# power.net
KiCad netlist of a schematic drawn in EAGLE
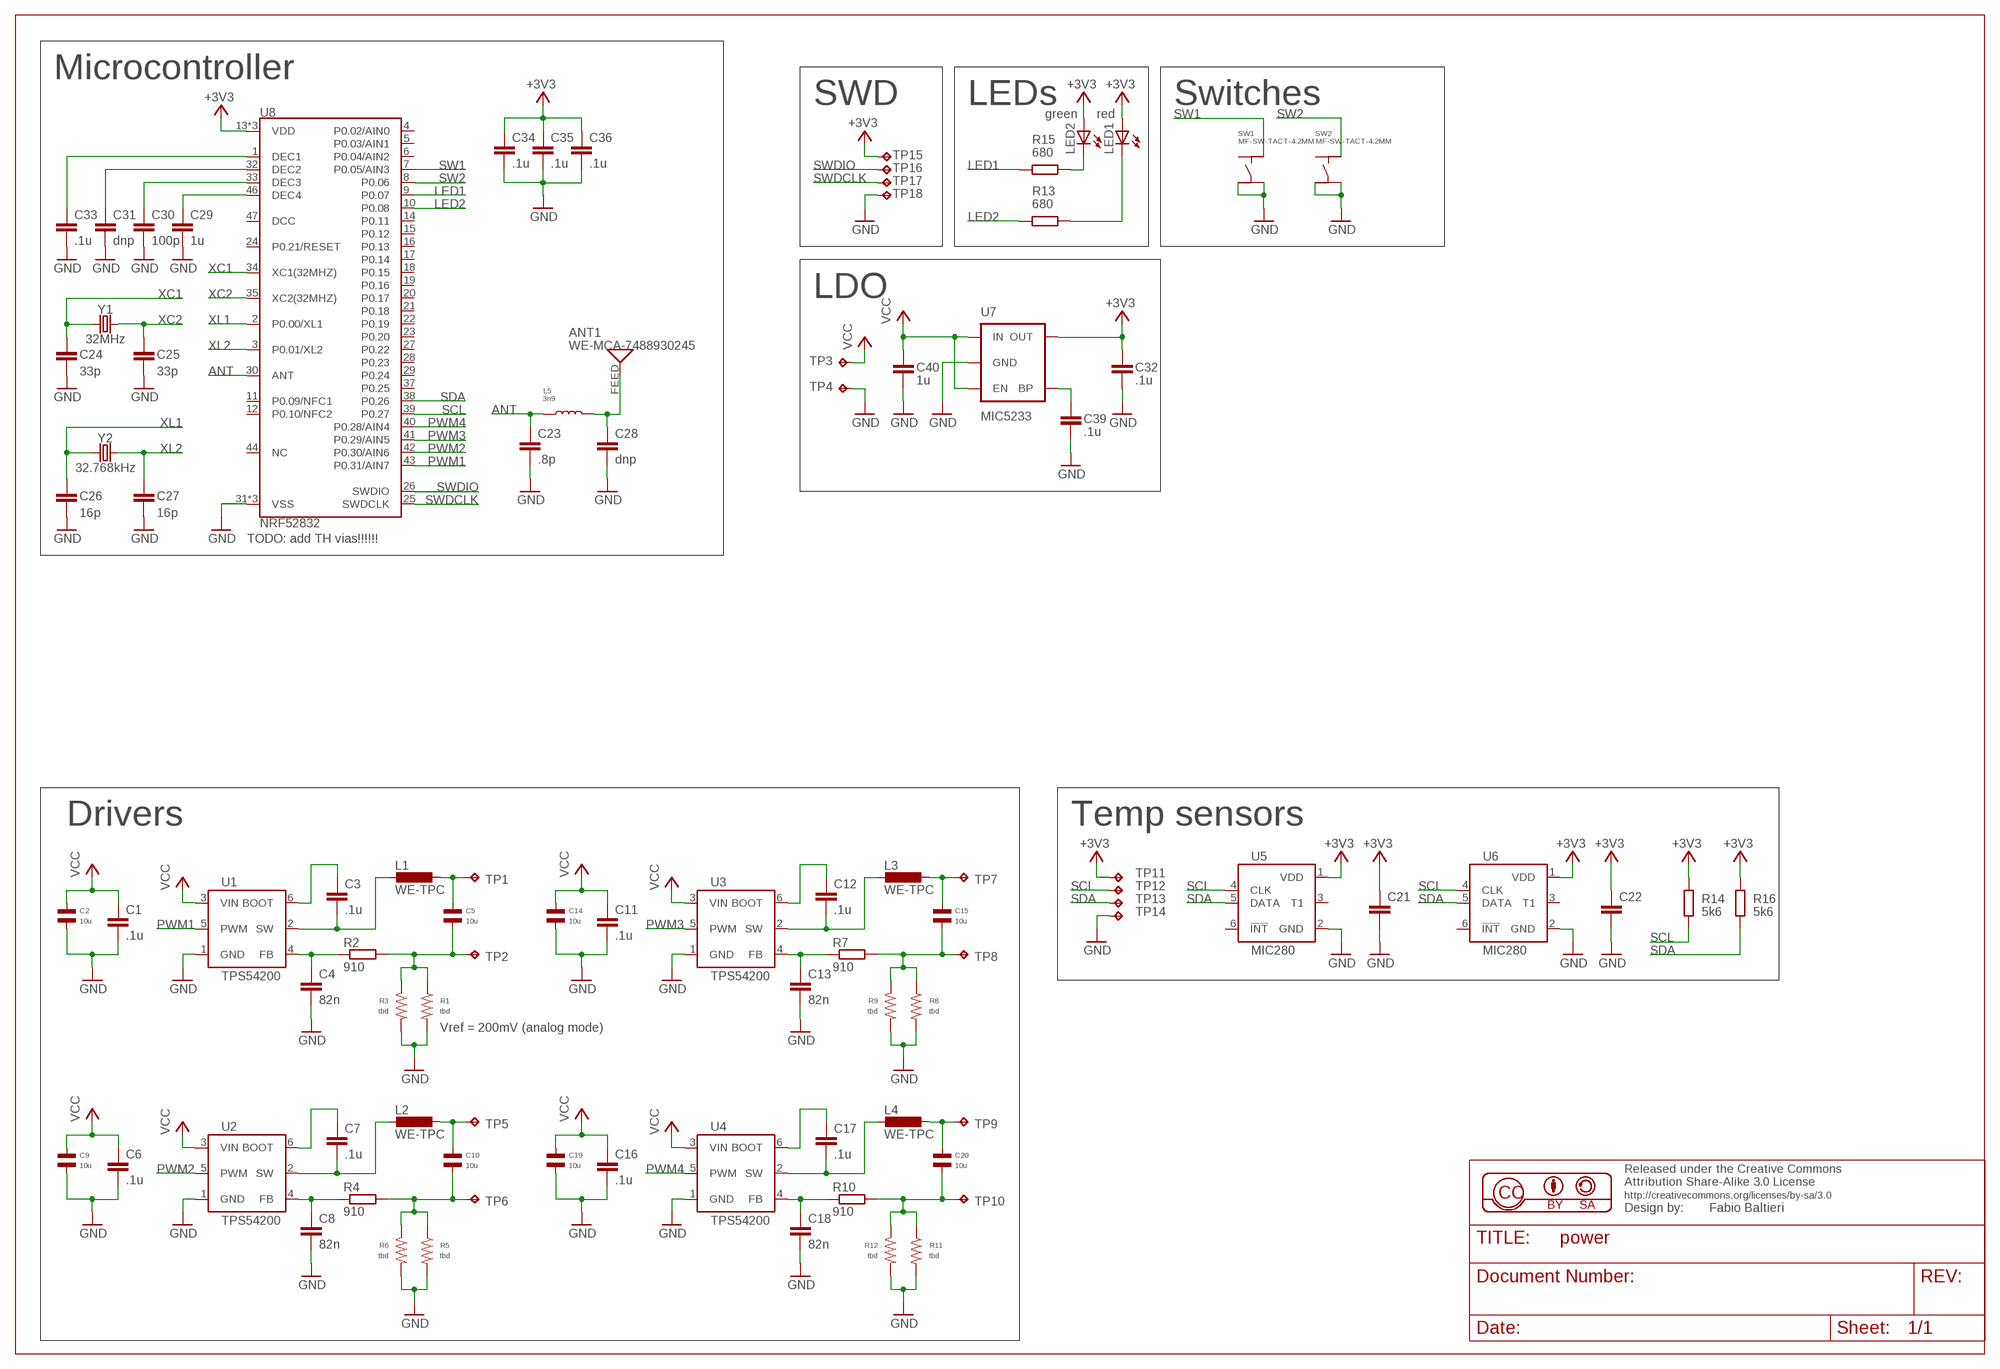
[diagram p0: schematic, sheet 1]

(export (version "E")
  (design (tool "Eeschema 10.0.6"))
  (components
    (comp (ref "ANT1")
      (value "WE-MCA-7488930245")
      (footprint "eagle-import:WE-MCA")
      (libsource (lib "eagle-import") (part "WE-MCA-7488930245"))
    )
    (comp (ref "C1")
      (value ".1u")
      (footprint "eagle-import:0603")
      (libsource (lib "eagle-import") (part "C0603"))
    )
    (comp (ref "C2")
      (value "10u")
      (footprint "eagle-import:C1206")
      (libsource (lib "eagle-import") (part "CAPACITOR_NP_1206"))
    )
    (comp (ref "C3")
      (value ".1u")
      (footprint "eagle-import:0603")
      (libsource (lib "eagle-import") (part "C0603"))
    )
    (comp (ref "C4")
      (value "82n")
      (footprint "eagle-import:0603")
      (libsource (lib "eagle-import") (part "C0603"))
    )
    (comp (ref "C5")
      (value "10u")
      (footprint "eagle-import:C1206")
      (libsource (lib "eagle-import") (part "CAPACITOR_NP_1206"))
    )
    (comp (ref "C6")
      (value ".1u")
      (footprint "eagle-import:0603")
      (libsource (lib "eagle-import") (part "C0603"))
    )
    (comp (ref "C7")
      (value ".1u")
      (footprint "eagle-import:0603")
      (libsource (lib "eagle-import") (part "C0603"))
    )
    (comp (ref "C8")
      (value "82n")
      (footprint "eagle-import:0603")
      (libsource (lib "eagle-import") (part "C0603"))
    )
    (comp (ref "C9")
      (value "10u")
      (footprint "eagle-import:C1206")
      (libsource (lib "eagle-import") (part "CAPACITOR_NP_1206"))
    )
    (comp (ref "C10")
      (value "10u")
      (footprint "eagle-import:C1206")
      (libsource (lib "eagle-import") (part "CAPACITOR_NP_1206"))
    )
    (comp (ref "C11")
      (value ".1u")
      (footprint "eagle-import:0603")
      (libsource (lib "eagle-import") (part "C0603"))
    )
    (comp (ref "C12")
      (value ".1u")
      (footprint "eagle-import:0603")
      (libsource (lib "eagle-import") (part "C0603"))
    )
    (comp (ref "C13")
      (value "82n")
      (footprint "eagle-import:0603")
      (libsource (lib "eagle-import") (part "C0603"))
    )
    (comp (ref "C14")
      (value "10u")
      (footprint "eagle-import:C1206")
      (libsource (lib "eagle-import") (part "CAPACITOR_NP_1206"))
    )
    (comp (ref "C15")
      (value "10u")
      (footprint "eagle-import:C1206")
      (libsource (lib "eagle-import") (part "CAPACITOR_NP_1206"))
    )
    (comp (ref "C16")
      (value ".1u")
      (footprint "eagle-import:0603")
      (libsource (lib "eagle-import") (part "C0603"))
    )
    (comp (ref "C17")
      (value ".1u")
      (footprint "eagle-import:0603")
      (libsource (lib "eagle-import") (part "C0603"))
    )
    (comp (ref "C18")
      (value "82n")
      (footprint "eagle-import:0603")
      (libsource (lib "eagle-import") (part "C0603"))
    )
    (comp (ref "C19")
      (value "10u")
      (footprint "eagle-import:C1206")
      (libsource (lib "eagle-import") (part "CAPACITOR_NP_1206"))
    )
    (comp (ref "C20")
      (value "10u")
      (footprint "eagle-import:C1206")
      (libsource (lib "eagle-import") (part "CAPACITOR_NP_1206"))
    )
    (comp (ref "C21")
      (value "C0603")
      (footprint "eagle-import:0603")
      (libsource (lib "eagle-import") (part "C0603"))
    )
    (comp (ref "C22")
      (value "C0603")
      (footprint "eagle-import:0603")
      (libsource (lib "eagle-import") (part "C0603"))
    )
    (comp (ref "C23")
      (value ".8p")
      (footprint "eagle-import:0603")
      (libsource (lib "eagle-import") (part "C0603"))
    )
    (comp (ref "C24")
      (value "33p")
      (footprint "eagle-import:0603")
      (libsource (lib "eagle-import") (part "C0603"))
    )
    (comp (ref "C25")
      (value "33p")
      (footprint "eagle-import:0603")
      (libsource (lib "eagle-import") (part "C0603"))
    )
    (comp (ref "C26")
      (value "16p")
      (footprint "eagle-import:0603")
      (libsource (lib "eagle-import") (part "C0603"))
    )
    (comp (ref "C27")
      (value "16p")
      (footprint "eagle-import:0603")
      (libsource (lib "eagle-import") (part "C0603"))
    )
    (comp (ref "C28")
      (value "dnp")
      (footprint "eagle-import:0603")
      (libsource (lib "eagle-import") (part "C0603"))
    )
    (comp (ref "C29")
      (value "1u")
      (footprint "eagle-import:0603")
      (libsource (lib "eagle-import") (part "C0603"))
    )
    (comp (ref "C30")
      (value "100p")
      (footprint "eagle-import:0603")
      (libsource (lib "eagle-import") (part "C0603"))
    )
    (comp (ref "C31")
      (value "dnp")
      (footprint "eagle-import:0603")
      (libsource (lib "eagle-import") (part "C0603"))
    )
    (comp (ref "C32")
      (value ".1u")
      (footprint "eagle-import:0603")
      (libsource (lib "eagle-import") (part "C0603"))
    )
    (comp (ref "C33")
      (value ".1u")
      (footprint "eagle-import:0603")
      (libsource (lib "eagle-import") (part "C0603"))
    )
    (comp (ref "C34")
      (value ".1u")
      (footprint "eagle-import:0603")
      (libsource (lib "eagle-import") (part "C0603"))
    )
    (comp (ref "C35")
      (value ".1u")
      (footprint "eagle-import:0603")
      (libsource (lib "eagle-import") (part "C0603"))
    )
    (comp (ref "C36")
      (value ".1u")
      (footprint "eagle-import:0603")
      (libsource (lib "eagle-import") (part "C0603"))
    )
    (comp (ref "C39")
      (value ".1u")
      (footprint "eagle-import:0603")
      (libsource (lib "eagle-import") (part "C0603"))
    )
    (comp (ref "C40")
      (value "1u")
      (footprint "eagle-import:0603")
      (libsource (lib "eagle-import") (part "C0603"))
    )
    (comp (ref "L1")
      (value "WE-TPC")
      (footprint "eagle-import:WE-TPC_INDUCTOR")
      (libsource (lib "eagle-import") (part "WE-TPC"))
    )
    (comp (ref "L2")
      (value "WE-TPC")
      (footprint "eagle-import:WE-TPC_INDUCTOR")
      (libsource (lib "eagle-import") (part "WE-TPC"))
    )
    (comp (ref "L3")
      (value "WE-TPC")
      (footprint "eagle-import:WE-TPC_INDUCTOR")
      (libsource (lib "eagle-import") (part "WE-TPC"))
    )
    (comp (ref "L4")
      (value "WE-TPC")
      (footprint "eagle-import:WE-TPC_INDUCTOR")
      (libsource (lib "eagle-import") (part "WE-TPC"))
    )
    (comp (ref "L5")
      (value "3n9")
      (footprint "eagle-import:L0603")
      (libsource (lib "eagle-import") (part "INDUCTOR_0603"))
    )
    (comp (ref "LED1")
      (value "LEDSML0805")
      (footprint "eagle-import:SML0805")
      (libsource (lib "eagle-import") (part "LEDSML0805"))
    )
    (comp (ref "LED2")
      (value "LEDSML0805")
      (footprint "eagle-import:SML0805")
      (libsource (lib "eagle-import") (part "LEDSML0805"))
    )
    (comp (ref "R1")
      (value "tbd")
      (footprint "eagle-import:R0805")
      (libsource (lib "eagle-import") (part "RESISTOR_0805"))
    )
    (comp (ref "R2")
      (value "910")
      (footprint "eagle-import:0603")
      (libsource (lib "eagle-import") (part "R0603"))
    )
    (comp (ref "R3")
      (value "tbd")
      (footprint "eagle-import:R0805")
      (libsource (lib "eagle-import") (part "RESISTOR_0805"))
    )
    (comp (ref "R4")
      (value "910")
      (footprint "eagle-import:0603")
      (libsource (lib "eagle-import") (part "R0603"))
    )
    (comp (ref "R5")
      (value "tbd")
      (footprint "eagle-import:R0805")
      (libsource (lib "eagle-import") (part "RESISTOR_0805"))
    )
    (comp (ref "R6")
      (value "tbd")
      (footprint "eagle-import:R0805")
      (libsource (lib "eagle-import") (part "RESISTOR_0805"))
    )
    (comp (ref "R7")
      (value "910")
      (footprint "eagle-import:0603")
      (libsource (lib "eagle-import") (part "R0603"))
    )
    (comp (ref "R8")
      (value "tbd")
      (footprint "eagle-import:R0805")
      (libsource (lib "eagle-import") (part "RESISTOR_0805"))
    )
    (comp (ref "R9")
      (value "tbd")
      (footprint "eagle-import:R0805")
      (libsource (lib "eagle-import") (part "RESISTOR_0805"))
    )
    (comp (ref "R10")
      (value "910")
      (footprint "eagle-import:0603")
      (libsource (lib "eagle-import") (part "R0603"))
    )
    (comp (ref "R11")
      (value "tbd")
      (footprint "eagle-import:R0805")
      (libsource (lib "eagle-import") (part "RESISTOR_0805"))
    )
    (comp (ref "R12")
      (value "tbd")
      (footprint "eagle-import:R0805")
      (libsource (lib "eagle-import") (part "RESISTOR_0805"))
    )
    (comp (ref "R13")
      (value "680")
      (footprint "eagle-import:0603")
      (libsource (lib "eagle-import") (part "R0603"))
    )
    (comp (ref "R14")
      (value "5k6")
      (footprint "eagle-import:0603")
      (libsource (lib "eagle-import") (part "R0603"))
    )
    (comp (ref "R15")
      (value "680")
      (footprint "eagle-import:0603")
      (libsource (lib "eagle-import") (part "R0603"))
    )
    (comp (ref "R16")
      (value "5k6")
      (footprint "eagle-import:0603")
      (libsource (lib "eagle-import") (part "R0603"))
    )
    (comp (ref "SW1")
      (value "MF-SW-TACT-4.2MM")
      (footprint "eagle-import:TACT4.2MM")
      (fields (field (name "HOUSEPART") "YES"))
      (libsource (lib "eagle-import") (part "TACT_4.2MM"))
    )
    (comp (ref "SW2")
      (value "MF-SW-TACT-4.2MM")
      (footprint "eagle-import:TACT4.2MM")
      (fields (field (name "HOUSEPART") "YES"))
      (libsource (lib "eagle-import") (part "TACT_4.2MM"))
    )
    (comp (ref "TP1")
      (value "TPTP18R")
      (footprint "eagle-import:TP18R")
      (libsource (lib "eagle-import") (part "testpad_385_TPTP18R"))
    )
    (comp (ref "TP2")
      (value "TPTP18R")
      (footprint "eagle-import:TP18R")
      (libsource (lib "eagle-import") (part "testpad_385_TPTP18R"))
    )
    (comp (ref "TP3")
      (value "TPTP18R")
      (footprint "eagle-import:TP18R")
      (libsource (lib "eagle-import") (part "testpad_385_TPTP18R"))
    )
    (comp (ref "TP4")
      (value "TPTP18R")
      (footprint "eagle-import:TP18R")
      (libsource (lib "eagle-import") (part "testpad_385_TPTP18R"))
    )
    (comp (ref "TP5")
      (value "TPTP18R")
      (footprint "eagle-import:TP18R")
      (libsource (lib "eagle-import") (part "testpad_385_TPTP18R"))
    )
    (comp (ref "TP6")
      (value "TPTP18R")
      (footprint "eagle-import:TP18R")
      (libsource (lib "eagle-import") (part "testpad_385_TPTP18R"))
    )
    (comp (ref "TP7")
      (value "TPTP18R")
      (footprint "eagle-import:TP18R")
      (libsource (lib "eagle-import") (part "testpad_385_TPTP18R"))
    )
    (comp (ref "TP8")
      (value "TPTP18R")
      (footprint "eagle-import:TP18R")
      (libsource (lib "eagle-import") (part "testpad_385_TPTP18R"))
    )
    (comp (ref "TP9")
      (value "TPTP18R")
      (footprint "eagle-import:TP18R")
      (libsource (lib "eagle-import") (part "testpad_385_TPTP18R"))
    )
    (comp (ref "TP10")
      (value "TPTP18R")
      (footprint "eagle-import:TP18R")
      (libsource (lib "eagle-import") (part "testpad_385_TPTP18R"))
    )
    (comp (ref "TP11")
      (value "TPTP14R")
      (footprint "eagle-import:TP14R")
      (libsource (lib "eagle-import") (part "testpad_385_TPTP14R"))
    )
    (comp (ref "TP12")
      (value "TPTP14R")
      (footprint "eagle-import:TP14R")
      (libsource (lib "eagle-import") (part "testpad_385_TPTP14R"))
    )
    (comp (ref "TP13")
      (value "TPTP14R")
      (footprint "eagle-import:TP14R")
      (libsource (lib "eagle-import") (part "testpad_385_TPTP14R"))
    )
    (comp (ref "TP14")
      (value "TPTP14R")
      (footprint "eagle-import:TP14R")
      (libsource (lib "eagle-import") (part "testpad_385_TPTP14R"))
    )
    (comp (ref "TP15")
      (value "TPTP12R")
      (footprint "eagle-import:TP12R")
      (libsource (lib "eagle-import") (part "TPTP12R"))
    )
    (comp (ref "TP16")
      (value "TPTP12R")
      (footprint "eagle-import:TP12R")
      (libsource (lib "eagle-import") (part "TPTP12R"))
    )
    (comp (ref "TP17")
      (value "TPTP12R")
      (footprint "eagle-import:TP12R")
      (libsource (lib "eagle-import") (part "TPTP12R"))
    )
    (comp (ref "TP18")
      (value "TPTP12R")
      (footprint "eagle-import:TP12R")
      (libsource (lib "eagle-import") (part "TPTP12R"))
    )
    (comp (ref "U1")
      (value "TPS54200")
      (footprint "eagle-import:SOT23-6L")
      (libsource (lib "eagle-import") (part "TPS54200"))
    )
    (comp (ref "U2")
      (value "TPS54200")
      (footprint "eagle-import:SOT23-6L")
      (libsource (lib "eagle-import") (part "TPS54200"))
    )
    (comp (ref "U3")
      (value "TPS54200")
      (footprint "eagle-import:SOT23-6L")
      (libsource (lib "eagle-import") (part "TPS54200"))
    )
    (comp (ref "U4")
      (value "TPS54200")
      (footprint "eagle-import:SOT23-6L")
      (libsource (lib "eagle-import") (part "TPS54200"))
    )
    (comp (ref "U5")
      (value "MIC280")
      (footprint "eagle-import:SOT23-6L")
      (libsource (lib "eagle-import") (part "MIC280"))
    )
    (comp (ref "U6")
      (value "MIC280")
      (footprint "eagle-import:SOT23-6L")
      (libsource (lib "eagle-import") (part "MIC280"))
    )
    (comp (ref "U7")
      (value "MIC5233")
      (footprint "eagle-import:SOT23-5")
      (libsource (lib "eagle-import") (part "V_REG_LDOSMD"))
    )
    (comp (ref "U8")
      (value "NRF52832")
      (footprint "eagle-import:QFN48-6X6MM")
      (libsource (lib "eagle-import") (part "NRF52832"))
    )
    (comp (ref "Y1")
      (value "32MHz")
      (footprint "eagle-import:CRYSTAL-SMD-3.2X2.5MM")
      (libsource (lib "eagle-import") (part "CRYSTALSMD-3.2X2.5"))
    )
    (comp (ref "Y2")
      (value "32.768kHz")
      (footprint "eagle-import:CRYSTAL-SMD-3.2X1.5MM")
      (libsource (lib "eagle-import") (part "CRYSTAL-32.768KHZSMD-3.2X1.5"))
    )
  )
  (nets
    (net (code "1") (name "+3V3") (class "Default")
      (node (ref "C21") (pin "1") (pinfunction "1_1") (pintype "passive"))
      (node (ref "C22") (pin "1") (pinfunction "1_1") (pintype "passive"))
      (node (ref "C32") (pin "1") (pinfunction "1_1") (pintype "passive"))
      (node (ref "C34") (pin "1") (pinfunction "1_1") (pintype "passive"))
      (node (ref "C35") (pin "1") (pinfunction "1_1") (pintype "passive"))
      (node (ref "C36") (pin "1") (pinfunction "1_1") (pintype "passive"))
      (node (ref "LED1") (pin "A") (pinfunction "A_A") (pintype "passive"))
      (node (ref "LED2") (pin "A") (pinfunction "A_A") (pintype "passive"))
      (node (ref "R14") (pin "1") (pinfunction "1_1") (pintype "passive"))
      (node (ref "R16") (pin "1") (pinfunction "1_1") (pintype "passive"))
      (node (ref "TP11") (pin "TP") (pinfunction "TP_TP") (pintype "input"))
      (node (ref "TP15") (pin "TP") (pinfunction "TP_TP") (pintype "input"))
      (node (ref "U5") (pin "1") (pinfunction "VDD_1") (pintype "bidirectional"))
      (node (ref "U6") (pin "1") (pinfunction "VDD_1") (pintype "bidirectional"))
      (node (ref "U7") (pin "5") (pinfunction "OUT_5") (pintype "passive"))
      (node (ref "U8") (pin "13") (pinfunction "VDD_13") (pintype "bidirectional"))
      (node (ref "U8") (pin "36") (pinfunction "VDD_36") (pintype "bidirectional"))
      (node (ref "U8") (pin "48") (pinfunction "VDD_48") (pintype "bidirectional"))
    )
    (net (code "2") (name "/ANT") (class "Default")
      (node (ref "C23") (pin "1") (pinfunction "1_1") (pintype "passive"))
      (node (ref "L5") (pin "P$1") (pinfunction "P$1_P$1") (pintype "passive"))
      (node (ref "U8") (pin "30") (pinfunction "ANT_30") (pintype "bidirectional"))
    )
    (net (code "3") (name "/LED1") (class "Default")
      (node (ref "R15") (pin "2") (pinfunction "2_2") (pintype "passive"))
      (node (ref "U8") (pin "9") (pinfunction "P0.07_9") (pintype "bidirectional"))
    )
    (net (code "4") (name "/LED2") (class "Default")
      (node (ref "R13") (pin "2") (pinfunction "2_2") (pintype "passive"))
      (node (ref "U8") (pin "10") (pinfunction "P0.08_10") (pintype "bidirectional"))
    )
    (net (code "5") (name "/PWM1") (class "Default")
      (node (ref "U1") (pin "5") (pinfunction "PWM_5") (pintype "bidirectional"))
      (node (ref "U8") (pin "43") (pinfunction "P0.31/AIN7_43") (pintype "bidirectional"))
    )
    (net (code "6") (name "/PWM2") (class "Default")
      (node (ref "U2") (pin "5") (pinfunction "PWM_5") (pintype "bidirectional"))
      (node (ref "U8") (pin "42") (pinfunction "P0.30/AIN6_42") (pintype "bidirectional"))
    )
    (net (code "7") (name "/PWM3") (class "Default")
      (node (ref "U3") (pin "5") (pinfunction "PWM_5") (pintype "bidirectional"))
      (node (ref "U8") (pin "41") (pinfunction "P0.29/AIN5_41") (pintype "bidirectional"))
    )
    (net (code "8") (name "/PWM4") (class "Default")
      (node (ref "U4") (pin "5") (pinfunction "PWM_5") (pintype "bidirectional"))
      (node (ref "U8") (pin "40") (pinfunction "P0.28/AIN4_40") (pintype "bidirectional"))
    )
    (net (code "9") (name "/SCL") (class "Default")
      (node (ref "R14") (pin "2") (pinfunction "2_2") (pintype "passive"))
      (node (ref "TP12") (pin "TP") (pinfunction "TP_TP") (pintype "input"))
      (node (ref "U5") (pin "4") (pinfunction "CLK_4") (pintype "bidirectional"))
      (node (ref "U6") (pin "4") (pinfunction "CLK_4") (pintype "bidirectional"))
      (node (ref "U8") (pin "39") (pinfunction "P0.27_39") (pintype "bidirectional"))
    )
    (net (code "10") (name "/SDA") (class "Default")
      (node (ref "R16") (pin "2") (pinfunction "2_2") (pintype "passive"))
      (node (ref "TP13") (pin "TP") (pinfunction "TP_TP") (pintype "input"))
      (node (ref "U5") (pin "5") (pinfunction "DATA_5") (pintype "bidirectional"))
      (node (ref "U6") (pin "5") (pinfunction "DATA_5") (pintype "bidirectional"))
      (node (ref "U8") (pin "38") (pinfunction "P0.26_38") (pintype "bidirectional"))
    )
    (net (code "11") (name "/SW1") (class "Default")
      (node (ref "SW1") (pin "P$2") (pinfunction "P$2_P$2") (pintype "bidirectional"))
      (node (ref "U8") (pin "7") (pinfunction "P0.05/AIN3_7") (pintype "bidirectional"))
    )
    (net (code "12") (name "/SW2") (class "Default")
      (node (ref "SW2") (pin "P$2") (pinfunction "P$2_P$2") (pintype "bidirectional"))
      (node (ref "U8") (pin "8") (pinfunction "P0.06_8") (pintype "bidirectional"))
    )
    (net (code "13") (name "/SWDCLK") (class "Default")
      (node (ref "TP17") (pin "TP") (pinfunction "TP_TP") (pintype "input"))
      (node (ref "U8") (pin "25") (pinfunction "SWDCLK_25") (pintype "bidirectional"))
    )
    (net (code "14") (name "/SWDIO") (class "Default")
      (node (ref "TP16") (pin "TP") (pinfunction "TP_TP") (pintype "input"))
      (node (ref "U8") (pin "26") (pinfunction "SWDIO_26") (pintype "bidirectional"))
    )
    (net (code "15") (name "/XC1") (class "Default")
      (node (ref "C24") (pin "1") (pinfunction "1_1") (pintype "passive"))
      (node (ref "U8") (pin "34") (pinfunction "XC1(32MHZ)_34") (pintype "bidirectional"))
      (node (ref "Y1") (pin "1") (pinfunction "1_1") (pintype "passive"))
    )
    (net (code "16") (name "/XC2") (class "Default")
      (node (ref "C25") (pin "1") (pinfunction "1_1") (pintype "passive"))
      (node (ref "U8") (pin "35") (pinfunction "XC2(32MHZ)_35") (pintype "bidirectional"))
      (node (ref "Y1") (pin "3") (pinfunction "2_3") (pintype "passive"))
    )
    (net (code "17") (name "/XL1") (class "Default")
      (node (ref "C26") (pin "1") (pinfunction "1_1") (pintype "passive"))
      (node (ref "U8") (pin "2") (pinfunction "P0.00/XL1_2") (pintype "bidirectional"))
      (node (ref "Y2") (pin "P$1") (pinfunction "1_P$1") (pintype "passive"))
    )
    (net (code "18") (name "/XL2") (class "Default")
      (node (ref "C27") (pin "1") (pinfunction "1_1") (pintype "passive"))
      (node (ref "U8") (pin "3") (pinfunction "P0.01/XL2_3") (pintype "bidirectional"))
      (node (ref "Y2") (pin "P$2") (pinfunction "2_P$2") (pintype "passive"))
    )
    (net (code "19") (name "GND") (class "Default")
      (node (ref "C1") (pin "2") (pinfunction "2_2") (pintype "passive"))
      (node (ref "C11") (pin "2") (pinfunction "2_2") (pintype "passive"))
      (node (ref "C13") (pin "2") (pinfunction "2_2") (pintype "passive"))
      (node (ref "C14") (pin "P$2") (pinfunction "P$2_P$2") (pintype "passive"))
      (node (ref "C16") (pin "2") (pinfunction "2_2") (pintype "passive"))
      (node (ref "C18") (pin "2") (pinfunction "2_2") (pintype "passive"))
      (node (ref "C19") (pin "P$2") (pinfunction "P$2_P$2") (pintype "passive"))
      (node (ref "C2") (pin "P$2") (pinfunction "P$2_P$2") (pintype "passive"))
      (node (ref "C21") (pin "2") (pinfunction "2_2") (pintype "passive"))
      (node (ref "C22") (pin "2") (pinfunction "2_2") (pintype "passive"))
      (node (ref "C23") (pin "2") (pinfunction "2_2") (pintype "passive"))
      (node (ref "C24") (pin "2") (pinfunction "2_2") (pintype "passive"))
      (node (ref "C25") (pin "2") (pinfunction "2_2") (pintype "passive"))
      (node (ref "C26") (pin "2") (pinfunction "2_2") (pintype "passive"))
      (node (ref "C27") (pin "2") (pinfunction "2_2") (pintype "passive"))
      (node (ref "C28") (pin "2") (pinfunction "2_2") (pintype "passive"))
      (node (ref "C29") (pin "2") (pinfunction "2_2") (pintype "passive"))
      (node (ref "C30") (pin "2") (pinfunction "2_2") (pintype "passive"))
      (node (ref "C31") (pin "2") (pinfunction "2_2") (pintype "passive"))
      (node (ref "C32") (pin "2") (pinfunction "2_2") (pintype "passive"))
      (node (ref "C33") (pin "2") (pinfunction "2_2") (pintype "passive"))
      (node (ref "C34") (pin "2") (pinfunction "2_2") (pintype "passive"))
      (node (ref "C35") (pin "2") (pinfunction "2_2") (pintype "passive"))
      (node (ref "C36") (pin "2") (pinfunction "2_2") (pintype "passive"))
      (node (ref "C39") (pin "2") (pinfunction "2_2") (pintype "passive"))
      (node (ref "C4") (pin "2") (pinfunction "2_2") (pintype "passive"))
      (node (ref "C40") (pin "2") (pinfunction "2_2") (pintype "passive"))
      (node (ref "C6") (pin "2") (pinfunction "2_2") (pintype "passive"))
      (node (ref "C8") (pin "2") (pinfunction "2_2") (pintype "passive"))
      (node (ref "C9") (pin "P$2") (pinfunction "P$2_P$2") (pintype "passive"))
      (node (ref "R1") (pin "P$2") (pinfunction "P$2_P$2") (pintype "passive"))
      (node (ref "R11") (pin "P$2") (pinfunction "P$2_P$2") (pintype "passive"))
      (node (ref "R12") (pin "P$2") (pinfunction "P$2_P$2") (pintype "passive"))
      (node (ref "R3") (pin "P$2") (pinfunction "P$2_P$2") (pintype "passive"))
      (node (ref "R5") (pin "P$2") (pinfunction "P$2_P$2") (pintype "passive"))
      (node (ref "R6") (pin "P$2") (pinfunction "P$2_P$2") (pintype "passive"))
      (node (ref "R8") (pin "P$2") (pinfunction "P$2_P$2") (pintype "passive"))
      (node (ref "R9") (pin "P$2") (pinfunction "P$2_P$2") (pintype "passive"))
      (node (ref "SW1") (pin "P$3") (pinfunction "P$3_P$3") (pintype "bidirectional"))
      (node (ref "SW1") (pin "P$4") (pinfunction "P$4_P$4") (pintype "bidirectional"))
      (node (ref "SW2") (pin "P$3") (pinfunction "P$3_P$3") (pintype "bidirectional"))
      (node (ref "SW2") (pin "P$4") (pinfunction "P$4_P$4") (pintype "bidirectional"))
      (node (ref "TP14") (pin "TP") (pinfunction "TP_TP") (pintype "input"))
      (node (ref "TP18") (pin "TP") (pinfunction "TP_TP") (pintype "input"))
      (node (ref "TP4") (pin "TP") (pinfunction "TP_TP") (pintype "input"))
      (node (ref "U1") (pin "1") (pinfunction "GND_1") (pintype "bidirectional"))
      (node (ref "U2") (pin "1") (pinfunction "GND_1") (pintype "bidirectional"))
      (node (ref "U3") (pin "1") (pinfunction "GND_1") (pintype "bidirectional"))
      (node (ref "U4") (pin "1") (pinfunction "GND_1") (pintype "bidirectional"))
      (node (ref "U5") (pin "2") (pinfunction "GND_2") (pintype "bidirectional"))
      (node (ref "U6") (pin "2") (pinfunction "GND_2") (pintype "bidirectional"))
      (node (ref "U7") (pin "2") (pinfunction "GND_2") (pintype "input"))
      (node (ref "U8") (pin "31") (pinfunction "VSS_31") (pintype "bidirectional"))
      (node (ref "U8") (pin "45") (pinfunction "VSS_45") (pintype "bidirectional"))
      (node (ref "U8") (pin "EP") (pinfunction "VSS_EP") (pintype "bidirectional"))
    )
    (net (code "20") (name "Net-(ANT1-P$1)") (class "Default")
      (node (ref "ANT1") (pin "FEED") (pinfunction "P$1_FEED") (pintype "bidirectional"))
      (node (ref "C28") (pin "1") (pinfunction "1_1") (pintype "passive"))
      (node (ref "L5") (pin "P$2") (pinfunction "P$2_P$2") (pintype "passive"))
    )
    (net (code "21") (name "Net-(C5-PadP$2)") (class "Default")
      (node (ref "C5") (pin "P$2") (pinfunction "P$2_P$2") (pintype "passive"))
      (node (ref "R1") (pin "P$1") (pinfunction "P$1_P$1") (pintype "passive"))
      (node (ref "R2") (pin "2") (pinfunction "2_2") (pintype "passive"))
      (node (ref "R3") (pin "P$1") (pinfunction "P$1_P$1") (pintype "passive"))
      (node (ref "TP2") (pin "TP") (pinfunction "TP_TP") (pintype "input"))
    )
    (net (code "22") (name "Net-(C10-PadP$2)") (class "Default")
      (node (ref "C10") (pin "P$2") (pinfunction "P$2_P$2") (pintype "passive"))
      (node (ref "R4") (pin "2") (pinfunction "2_2") (pintype "passive"))
      (node (ref "R5") (pin "P$1") (pinfunction "P$1_P$1") (pintype "passive"))
      (node (ref "R6") (pin "P$1") (pinfunction "P$1_P$1") (pintype "passive"))
      (node (ref "TP6") (pin "TP") (pinfunction "TP_TP") (pintype "input"))
    )
    (net (code "23") (name "Net-(C15-PadP$2)") (class "Default")
      (node (ref "C15") (pin "P$2") (pinfunction "P$2_P$2") (pintype "passive"))
      (node (ref "R7") (pin "2") (pinfunction "2_2") (pintype "passive"))
      (node (ref "R8") (pin "P$1") (pinfunction "P$1_P$1") (pintype "passive"))
      (node (ref "R9") (pin "P$1") (pinfunction "P$1_P$1") (pintype "passive"))
      (node (ref "TP8") (pin "TP") (pinfunction "TP_TP") (pintype "input"))
    )
    (net (code "24") (name "Net-(C20-PadP$2)") (class "Default")
      (node (ref "C20") (pin "P$2") (pinfunction "P$2_P$2") (pintype "passive"))
      (node (ref "R10") (pin "2") (pinfunction "2_2") (pintype "passive"))
      (node (ref "R11") (pin "P$1") (pinfunction "P$1_P$1") (pintype "passive"))
      (node (ref "R12") (pin "P$1") (pinfunction "P$1_P$1") (pintype "passive"))
      (node (ref "TP10") (pin "TP") (pinfunction "TP_TP") (pintype "input"))
    )
    (net (code "25") (name "Net-(L1-1)") (class "Default")
      (node (ref "C3") (pin "2") (pinfunction "2_2") (pintype "passive"))
      (node (ref "L1") (pin "P$1") (pinfunction "1_P$1") (pintype "passive"))
      (node (ref "U1") (pin "2") (pinfunction "SW_2") (pintype "bidirectional"))
    )
    (net (code "26") (name "Net-(L1-2)") (class "Default")
      (node (ref "C5") (pin "P$1") (pinfunction "P$1_P$1") (pintype "passive"))
      (node (ref "L1") (pin "P$2") (pinfunction "2_P$2") (pintype "passive"))
      (node (ref "TP1") (pin "TP") (pinfunction "TP_TP") (pintype "input"))
    )
    (net (code "27") (name "Net-(L2-1)") (class "Default")
      (node (ref "C7") (pin "2") (pinfunction "2_2") (pintype "passive"))
      (node (ref "L2") (pin "P$1") (pinfunction "1_P$1") (pintype "passive"))
      (node (ref "U2") (pin "2") (pinfunction "SW_2") (pintype "bidirectional"))
    )
    (net (code "28") (name "Net-(L2-2)") (class "Default")
      (node (ref "C10") (pin "P$1") (pinfunction "P$1_P$1") (pintype "passive"))
      (node (ref "L2") (pin "P$2") (pinfunction "2_P$2") (pintype "passive"))
      (node (ref "TP5") (pin "TP") (pinfunction "TP_TP") (pintype "input"))
    )
    (net (code "29") (name "Net-(L3-1)") (class "Default")
      (node (ref "C12") (pin "2") (pinfunction "2_2") (pintype "passive"))
      (node (ref "L3") (pin "P$1") (pinfunction "1_P$1") (pintype "passive"))
      (node (ref "U3") (pin "2") (pinfunction "SW_2") (pintype "bidirectional"))
    )
    (net (code "30") (name "Net-(L3-2)") (class "Default")
      (node (ref "C15") (pin "P$1") (pinfunction "P$1_P$1") (pintype "passive"))
      (node (ref "L3") (pin "P$2") (pinfunction "2_P$2") (pintype "passive"))
      (node (ref "TP7") (pin "TP") (pinfunction "TP_TP") (pintype "input"))
    )
    (net (code "31") (name "Net-(L4-1)") (class "Default")
      (node (ref "C17") (pin "2") (pinfunction "2_2") (pintype "passive"))
      (node (ref "L4") (pin "P$1") (pinfunction "1_P$1") (pintype "passive"))
      (node (ref "U4") (pin "2") (pinfunction "SW_2") (pintype "bidirectional"))
    )
    (net (code "32") (name "Net-(L4-2)") (class "Default")
      (node (ref "C20") (pin "P$1") (pinfunction "P$1_P$1") (pintype "passive"))
      (node (ref "L4") (pin "P$2") (pinfunction "2_P$2") (pintype "passive"))
      (node (ref "TP9") (pin "TP") (pinfunction "TP_TP") (pintype "input"))
    )
    (net (code "33") (name "Net-(LED1-PadC)") (class "Default")
      (node (ref "LED1") (pin "C") (pinfunction "C_C") (pintype "passive"))
      (node (ref "R13") (pin "1") (pinfunction "1_1") (pintype "passive"))
    )
    (net (code "34") (name "Net-(LED2-PadC)") (class "Default")
      (node (ref "LED2") (pin "C") (pinfunction "C_C") (pintype "passive"))
      (node (ref "R15") (pin "1") (pinfunction "1_1") (pintype "passive"))
    )
    (net (code "35") (name "Net-(U1-BOOT)") (class "Default")
      (node (ref "C3") (pin "1") (pinfunction "1_1") (pintype "passive"))
      (node (ref "U1") (pin "6") (pinfunction "BOOT_6") (pintype "bidirectional"))
    )
    (net (code "36") (name "Net-(U1-FB)") (class "Default")
      (node (ref "C4") (pin "1") (pinfunction "1_1") (pintype "passive"))
      (node (ref "R2") (pin "1") (pinfunction "1_1") (pintype "passive"))
      (node (ref "U1") (pin "4") (pinfunction "FB_4") (pintype "bidirectional"))
    )
    (net (code "37") (name "Net-(U2-BOOT)") (class "Default")
      (node (ref "C7") (pin "1") (pinfunction "1_1") (pintype "passive"))
      (node (ref "U2") (pin "6") (pinfunction "BOOT_6") (pintype "bidirectional"))
    )
    (net (code "38") (name "Net-(U2-FB)") (class "Default")
      (node (ref "C8") (pin "1") (pinfunction "1_1") (pintype "passive"))
      (node (ref "R4") (pin "1") (pinfunction "1_1") (pintype "passive"))
      (node (ref "U2") (pin "4") (pinfunction "FB_4") (pintype "bidirectional"))
    )
    (net (code "39") (name "Net-(U3-BOOT)") (class "Default")
      (node (ref "C12") (pin "1") (pinfunction "1_1") (pintype "passive"))
      (node (ref "U3") (pin "6") (pinfunction "BOOT_6") (pintype "bidirectional"))
    )
    (net (code "40") (name "Net-(U3-FB)") (class "Default")
      (node (ref "C13") (pin "1") (pinfunction "1_1") (pintype "passive"))
      (node (ref "R7") (pin "1") (pinfunction "1_1") (pintype "passive"))
      (node (ref "U3") (pin "4") (pinfunction "FB_4") (pintype "bidirectional"))
    )
    (net (code "41") (name "Net-(U4-BOOT)") (class "Default")
      (node (ref "C17") (pin "1") (pinfunction "1_1") (pintype "passive"))
      (node (ref "U4") (pin "6") (pinfunction "BOOT_6") (pintype "bidirectional"))
    )
    (net (code "42") (name "Net-(U4-FB)") (class "Default")
      (node (ref "C18") (pin "1") (pinfunction "1_1") (pintype "passive"))
      (node (ref "R10") (pin "1") (pinfunction "1_1") (pintype "passive"))
      (node (ref "U4") (pin "4") (pinfunction "FB_4") (pintype "bidirectional"))
    )
    (net (code "43") (name "Net-(U7-BP)") (class "Default")
      (node (ref "C39") (pin "1") (pinfunction "1_1") (pintype "passive"))
      (node (ref "U7") (pin "4") (pinfunction "BP_4") (pintype "input"))
    )
    (net (code "44") (name "Net-(U8-DEC1)") (class "Default")
      (node (ref "C33") (pin "1") (pinfunction "1_1") (pintype "passive"))
      (node (ref "U8") (pin "1") (pinfunction "DEC1_1") (pintype "bidirectional"))
    )
    (net (code "45") (name "Net-(U8-DEC2)") (class "Default")
      (node (ref "C31") (pin "1") (pinfunction "1_1") (pintype "passive"))
      (node (ref "U8") (pin "32") (pinfunction "DEC2_32") (pintype "bidirectional"))
    )
    (net (code "46") (name "Net-(U8-DEC3)") (class "Default")
      (node (ref "C30") (pin "1") (pinfunction "1_1") (pintype "passive"))
      (node (ref "U8") (pin "33") (pinfunction "DEC3_33") (pintype "bidirectional"))
    )
    (net (code "47") (name "Net-(U8-DEC4)") (class "Default")
      (node (ref "C29") (pin "1") (pinfunction "1_1") (pintype "passive"))
      (node (ref "U8") (pin "46") (pinfunction "DEC4_46") (pintype "bidirectional"))
    )
    (net (code "48") (name "VCC") (class "Default")
      (node (ref "C1") (pin "1") (pinfunction "1_1") (pintype "passive"))
      (node (ref "C11") (pin "1") (pinfunction "1_1") (pintype "passive"))
      (node (ref "C14") (pin "P$1") (pinfunction "P$1_P$1") (pintype "passive"))
      (node (ref "C16") (pin "1") (pinfunction "1_1") (pintype "passive"))
      (node (ref "C19") (pin "P$1") (pinfunction "P$1_P$1") (pintype "passive"))
      (node (ref "C2") (pin "P$1") (pinfunction "P$1_P$1") (pintype "passive"))
      (node (ref "C40") (pin "1") (pinfunction "1_1") (pintype "passive"))
      (node (ref "C6") (pin "1") (pinfunction "1_1") (pintype "passive"))
      (node (ref "C9") (pin "P$1") (pinfunction "P$1_P$1") (pintype "passive"))
      (node (ref "TP3") (pin "TP") (pinfunction "TP_TP") (pintype "input"))
      (node (ref "U1") (pin "3") (pinfunction "VIN_3") (pintype "bidirectional"))
      (node (ref "U2") (pin "3") (pinfunction "VIN_3") (pintype "bidirectional"))
      (node (ref "U3") (pin "3") (pinfunction "VIN_3") (pintype "bidirectional"))
      (node (ref "U4") (pin "3") (pinfunction "VIN_3") (pintype "bidirectional"))
      (node (ref "U7") (pin "1") (pinfunction "IN_1") (pintype "input"))
      (node (ref "U7") (pin "3") (pinfunction "EN_3") (pintype "input"))
    )
    (net (code "49") (name "unconnected-(SW1-PadP$1)") (class "Default")
      (node (ref "SW1") (pin "P$1") (pinfunction "P$1_P$1") (pintype "bidirectional"))
    )
    (net (code "50") (name "unconnected-(SW2-PadP$1)") (class "Default")
      (node (ref "SW2") (pin "P$1") (pinfunction "P$1_P$1") (pintype "bidirectional"))
    )
    (net (code "51") (name "unconnected-(U5-T1-Pad3)") (class "Default")
      (node (ref "U5") (pin "3") (pinfunction "T1_3") (pintype "bidirectional"))
    )
    (net (code "52") (name "unconnected-(U5-~{INT}-Pad6)") (class "Default")
      (node (ref "U5") (pin "6") (pinfunction "~{INT}_6") (pintype "bidirectional"))
    )
    (net (code "53") (name "unconnected-(U6-T1-Pad3)") (class "Default")
      (node (ref "U6") (pin "3") (pinfunction "T1_3") (pintype "bidirectional"))
    )
    (net (code "54") (name "unconnected-(U6-~{INT}-Pad6)") (class "Default")
      (node (ref "U6") (pin "6") (pinfunction "~{INT}_6") (pintype "bidirectional"))
    )
    (net (code "55") (name "unconnected-(U8-DCC-Pad47)") (class "Default")
      (node (ref "U8") (pin "47") (pinfunction "DCC_47") (pintype "bidirectional"))
    )
    (net (code "56") (name "unconnected-(U8-NC-Pad44)") (class "Default")
      (node (ref "U8") (pin "44") (pinfunction "NC_44") (pintype "bidirectional"))
    )
    (net (code "57") (name "unconnected-(U8-P0.02{slash}AIN0-Pad4)") (class "Default")
      (node (ref "U8") (pin "4") (pinfunction "P0.02/AIN0_4") (pintype "bidirectional"))
    )
    (net (code "58") (name "unconnected-(U8-P0.03{slash}AIN1-Pad5)") (class "Default")
      (node (ref "U8") (pin "5") (pinfunction "P0.03/AIN1_5") (pintype "bidirectional"))
    )
    (net (code "59") (name "unconnected-(U8-P0.04{slash}AIN2-Pad6)") (class "Default")
      (node (ref "U8") (pin "6") (pinfunction "P0.04/AIN2_6") (pintype "bidirectional"))
    )
    (net (code "60") (name "unconnected-(U8-P0.09{slash}NFC1-Pad11)") (class "Default")
      (node (ref "U8") (pin "11") (pinfunction "P0.09/NFC1_11") (pintype "bidirectional"))
    )
    (net (code "61") (name "unconnected-(U8-P0.10{slash}NFC2-Pad12)") (class "Default")
      (node (ref "U8") (pin "12") (pinfunction "P0.10/NFC2_12") (pintype "bidirectional"))
    )
    (net (code "62") (name "unconnected-(U8-P0.11-Pad14)") (class "Default")
      (node (ref "U8") (pin "14") (pinfunction "P0.11_14") (pintype "bidirectional"))
    )
    (net (code "63") (name "unconnected-(U8-P0.12-Pad15)") (class "Default")
      (node (ref "U8") (pin "15") (pinfunction "P0.12_15") (pintype "bidirectional"))
    )
    (net (code "64") (name "unconnected-(U8-P0.13-Pad16)") (class "Default")
      (node (ref "U8") (pin "16") (pinfunction "P0.13_16") (pintype "bidirectional"))
    )
    (net (code "65") (name "unconnected-(U8-P0.14-Pad17)") (class "Default")
      (node (ref "U8") (pin "17") (pinfunction "P0.14_17") (pintype "bidirectional"))
    )
    (net (code "66") (name "unconnected-(U8-P0.15-Pad18)") (class "Default")
      (node (ref "U8") (pin "18") (pinfunction "P0.15_18") (pintype "bidirectional"))
    )
    (net (code "67") (name "unconnected-(U8-P0.16-Pad19)") (class "Default")
      (node (ref "U8") (pin "19") (pinfunction "P0.16_19") (pintype "bidirectional"))
    )
    (net (code "68") (name "unconnected-(U8-P0.17-Pad20)") (class "Default")
      (node (ref "U8") (pin "20") (pinfunction "P0.17_20") (pintype "bidirectional"))
    )
    (net (code "69") (name "unconnected-(U8-P0.18-Pad21)") (class "Default")
      (node (ref "U8") (pin "21") (pinfunction "P0.18_21") (pintype "bidirectional"))
    )
    (net (code "70") (name "unconnected-(U8-P0.19-Pad22)") (class "Default")
      (node (ref "U8") (pin "22") (pinfunction "P0.19_22") (pintype "bidirectional"))
    )
    (net (code "71") (name "unconnected-(U8-P0.20-Pad23)") (class "Default")
      (node (ref "U8") (pin "23") (pinfunction "P0.20_23") (pintype "bidirectional"))
    )
    (net (code "72") (name "unconnected-(U8-P0.21{slash}RESET-Pad24)") (class "Default")
      (node (ref "U8") (pin "24") (pinfunction "P0.21/RESET_24") (pintype "bidirectional"))
    )
    (net (code "73") (name "unconnected-(U8-P0.22-Pad27)") (class "Default")
      (node (ref "U8") (pin "27") (pinfunction "P0.22_27") (pintype "bidirectional"))
    )
    (net (code "74") (name "unconnected-(U8-P0.23-Pad28)") (class "Default")
      (node (ref "U8") (pin "28") (pinfunction "P0.23_28") (pintype "bidirectional"))
    )
    (net (code "75") (name "unconnected-(U8-P0.24-Pad29)") (class "Default")
      (node (ref "U8") (pin "29") (pinfunction "P0.24_29") (pintype "bidirectional"))
    )
    (net (code "76") (name "unconnected-(U8-P0.25-Pad37)") (class "Default")
      (node (ref "U8") (pin "37") (pinfunction "P0.25_37") (pintype "bidirectional"))
    )
  )
)
